# USB.net
KiCad netlist of a schematic drawn in Altium Designer
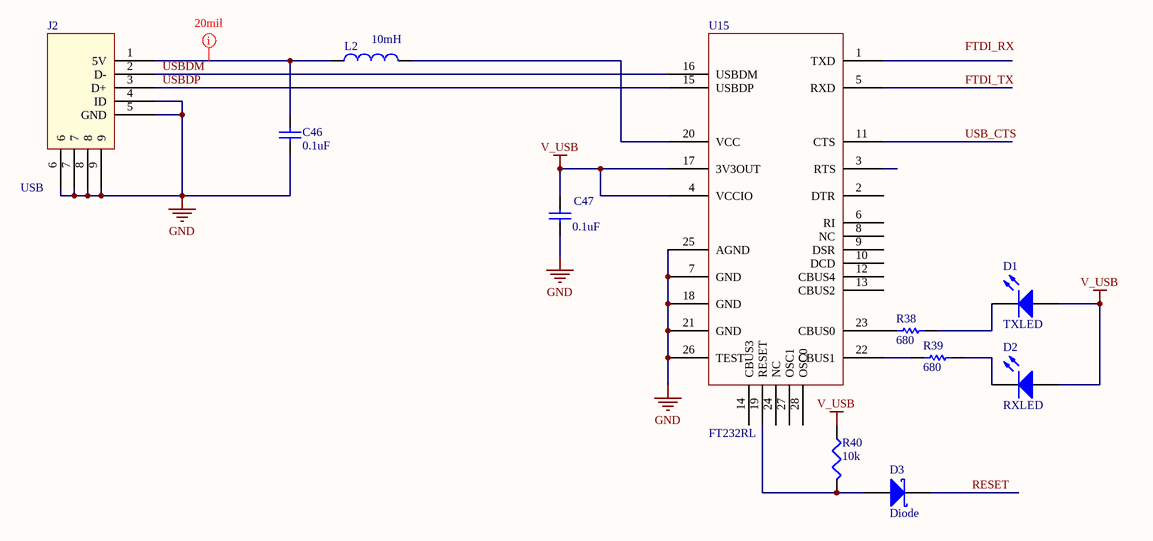
[diagram p0: USB.SchDoc]

(export (version "E")
  (design (tool "Eeschema 10.0.6"))
  (components
    (comp (ref "C46")
      (value "0.1uF")
      (footprint "CAPC1005L")
      (description "Capacitor")
      (fields (field (name "PUBLISHER") "Altium Limited"))
      (libsource (lib "Miscellaneous Devices") (part "Cap"))
    )
    (comp (ref "C47")
      (value "0.1uF")
      (footprint "CAPC1005L")
      (description "Capacitor")
      (fields (field (name "PUBLISHER") "Altium Limited"))
      (libsource (lib "Miscellaneous Devices") (part "Cap"))
    )
    (comp (ref "D1")
      (value "TXLED")
      (footprint "INDC2012L")
      (description "Typical RED, GREEN, YELLOW, AMBER GaAs LED")
      (fields (field (name "PUBLISHER") "Altium Limited"))
      (libsource (lib "Miscellaneous Devices") (part "LED2"))
    )
    (comp (ref "D2")
      (value "RXLED")
      (footprint "INDC2012L")
      (description "Typical RED, GREEN, YELLOW, AMBER GaAs LED")
      (fields (field (name "PUBLISHER") "Altium Limited"))
      (libsource (lib "Miscellaneous Devices") (part "LED2"))
    )
    (comp (ref "D3")
      (value "Diode")
      (footprint "SurfaceMount(603)")
      (libsource (lib "mrone") (part "SchottkeyDiode"))
    )
    (comp (ref "J2")
      (value "USB")
      (footprint "USB Minib (thru-hole)")
      (libsource (lib "mrone") (part "USB-ConnTH"))
    )
    (comp (ref "L2")
      (value "10mH")
      (footprint "INDC2012L")
      (description "Inductor")
      (fields (field (name "PUBLISHER") "Altium Limited"))
      (libsource (lib "Miscellaneous Devices") (part "Inductor"))
    )
    (comp (ref "R38")
      (value "680")
      (footprint "RESC1608L")
      (description "Resistor")
      (fields (field (name "PUBLISHER") "Altium Limited"))
      (libsource (lib "Miscellaneous Devices") (part "Res1"))
    )
    (comp (ref "R39")
      (value "680")
      (footprint "RESC1608L")
      (description "Resistor")
      (fields (field (name "PUBLISHER") "Altium Limited"))
      (libsource (lib "Miscellaneous Devices") (part "Res1"))
    )
    (comp (ref "R40")
      (value "10k")
      (footprint "RESC1608L")
      (description "Resistor")
      (fields (field (name "Comment") "Res3") (field (name "PUBLISHER") "Altium Limited"))
      (libsource (lib "Miscellaneous Devices") (part "Res3"))
    )
    (comp (ref "U15") (value "FT232RL") (footprint "SSOP-28") (libsource (lib "mrone") (part "FT232RL")))
  )
  (nets
    (net (code "2") (name "/FTDI_TX") (class "Default")
      (node (ref "U15") (pin "5") (pinfunction "RXD_5") (pintype "passive"))
    )
    (net (code "3") (name "/RESET") (class "Default")
      (node (ref "D3") (pin "1") (pinfunction "K_1") (pintype "passive"))
    )
    (net (code "4") (name "/USBDM") (class "Default")
      (node (ref "J2") (pin "2") (pinfunction "D-_2") (pintype "passive"))
      (node (ref "U15") (pin "16") (pinfunction "USBDM_16") (pintype "passive"))
    )
    (net (code "5") (name "/USBDP") (class "Default")
      (node (ref "J2") (pin "3") (pinfunction "D+_3") (pintype "passive"))
      (node (ref "U15") (pin "15") (pinfunction "USBDP_15") (pintype "passive"))
    )
    (net (code "6") (name "/USB_CTS") (class "Default")
      (node (ref "U15") (pin "11") (pinfunction "CTS_11") (pintype "passive"))
    )
    (net (code "7") (name "GND") (class "Default")
      (node (ref "C46") (pin "1") (pinfunction "1_1") (pintype "passive"))
      (node (ref "C47") (pin "1") (pinfunction "1_1") (pintype "passive"))
      (node (ref "J2") (pin "4") (pinfunction "ID_4") (pintype "passive"))
      (node (ref "J2") (pin "5") (pinfunction "GND_5") (pintype "passive"))
      (node (ref "J2") (pin "6") (pinfunction "6_6") (pintype "passive"))
      (node (ref "J2") (pin "7") (pinfunction "7_7") (pintype "passive"))
      (node (ref "J2") (pin "8") (pinfunction "8_8") (pintype "passive"))
      (node (ref "J2") (pin "9") (pinfunction "9_9") (pintype "passive"))
      (node (ref "U15") (pin "18") (pinfunction "GND_18") (pintype "passive"))
      (node (ref "U15") (pin "21") (pinfunction "GND_21") (pintype "passive"))
      (node (ref "U15") (pin "25") (pinfunction "AGND_25") (pintype "passive"))
      (node (ref "U15") (pin "26") (pinfunction "TEST_26") (pintype "passive"))
      (node (ref "U15") (pin "7") (pinfunction "GND_7") (pintype "passive"))
    )
    (net (code "8") (name "Net-(D1-K)") (class "Default")
      (node (ref "D1") (pin "2") (pinfunction "K_2") (pintype "passive"))
      (node (ref "R38") (pin "2") (pinfunction "2_2") (pintype "passive"))
    )
    (net (code "9") (name "Net-(D2-K)") (class "Default")
      (node (ref "D2") (pin "2") (pinfunction "K_2") (pintype "passive"))
      (node (ref "R39") (pin "2") (pinfunction "2_2") (pintype "passive"))
    )
    (net (code "10") (name "Net-(D3-A)") (class "Default")
      (node (ref "D3") (pin "3") (pinfunction "A_3") (pintype "passive"))
      (node (ref "R40") (pin "2") (pinfunction "2_2") (pintype "passive"))
      (node (ref "U15") (pin "19") (pinfunction "RESET_19") (pintype "passive"))
    )
    (net (code "11") (name "Net-(J2-5V)") (class "Default")
      (node (ref "C46") (pin "2") (pinfunction "2_2") (pintype "passive"))
      (node (ref "J2") (pin "1") (pinfunction "5V_1") (pintype "passive"))
      (node (ref "L2") (pin "1") (pinfunction "1_1") (pintype "passive"))
    )
    (net (code "12") (name "Net-(U15-CBUS0)") (class "Default")
      (node (ref "R38") (pin "1") (pinfunction "1_1") (pintype "passive"))
      (node (ref "U15") (pin "23") (pinfunction "CBUS0_23") (pintype "passive"))
    )
    (net (code "13") (name "Net-(U15-CBUS1)") (class "Default")
      (node (ref "R39") (pin "1") (pinfunction "1_1") (pintype "passive"))
      (node (ref "U15") (pin "22") (pinfunction "CBUS1_22") (pintype "passive"))
    )
    (net (code "14") (name "Net-(U15-VCC)") (class "Default")
      (node (ref "L2") (pin "2") (pinfunction "2_2") (pintype "passive"))
      (node (ref "U15") (pin "20") (pinfunction "VCC_20") (pintype "passive"))
    )
    (net (code "15") (name "V_USB") (class "Default")
      (node (ref "C47") (pin "2") (pinfunction "2_2") (pintype "passive"))
      (node (ref "D1") (pin "1") (pinfunction "A_1") (pintype "passive"))
      (node (ref "D2") (pin "1") (pinfunction "A_1") (pintype "passive"))
      (node (ref "R40") (pin "1") (pinfunction "1_1") (pintype "passive"))
      (node (ref "U15") (pin "17") (pinfunction "3V3OUT_17") (pintype "passive"))
      (node (ref "U15") (pin "4") (pinfunction "VCCIO_4") (pintype "passive"))
    )
    (net (code "16") (name "unconnected-(U15-CBUS2-Pad13)") (class "Default")
      (node (ref "U15") (pin "13") (pinfunction "CBUS2_13") (pintype "passive"))
    )
    (net (code "17") (name "unconnected-(U15-CBUS3-Pad14)") (class "Default")
      (node (ref "U15") (pin "14") (pinfunction "CBUS3_14") (pintype "passive"))
    )
    (net (code "18") (name "unconnected-(U15-CBUS4-Pad12)") (class "Default")
      (node (ref "U15") (pin "12") (pinfunction "CBUS4_12") (pintype "passive"))
    )
    (net (code "19") (name "unconnected-(U15-DCD-Pad10)") (class "Default")
      (node (ref "U15") (pin "10") (pinfunction "DCD_10") (pintype "passive"))
    )
    (net (code "20") (name "unconnected-(U15-DSR-Pad9)") (class "Default")
      (node (ref "U15") (pin "9") (pinfunction "DSR_9") (pintype "passive"))
    )
    (net (code "21") (name "unconnected-(U15-DTR-Pad2)") (class "Default")
      (node (ref "U15") (pin "2") (pinfunction "DTR_2") (pintype "passive"))
    )
    (net (code "22") (name "unconnected-(U15-NC-Pad8)") (class "Default")
      (node (ref "U15") (pin "8") (pinfunction "NC_8") (pintype "passive"))
    )
    (net (code "23") (name "unconnected-(U15-NC-Pad24)") (class "Default")
      (node (ref "U15") (pin "24") (pinfunction "NC_24") (pintype "passive"))
    )
    (net (code "24") (name "unconnected-(U15-OSC0-Pad28)") (class "Default")
      (node (ref "U15") (pin "28") (pinfunction "OSC0_28") (pintype "passive"))
    )
    (net (code "25") (name "unconnected-(U15-OSC1-Pad27)") (class "Default")
      (node (ref "U15") (pin "27") (pinfunction "OSC1_27") (pintype "passive"))
    )
    (net (code "26") (name "unconnected-(U15-RI-Pad6)") (class "Default")
      (node (ref "U15") (pin "6") (pinfunction "RI_6") (pintype "passive"))
    )
    (net (code "27") (name "unconnected-(U15-RTS-Pad3)") (class "Default")
      (node (ref "U15") (pin "3") (pinfunction "RTS_3") (pintype "passive"))
    )
    (net (code "28") (name "unconnected-(U15-TXD-Pad1)") (class "Default")
      (node (ref "U15") (pin "1") (pinfunction "TXD_1") (pintype "passive"))
    )
  )
)
